# Plant_Reminder.net
KiCad netlist of a schematic drawn in EAGLE
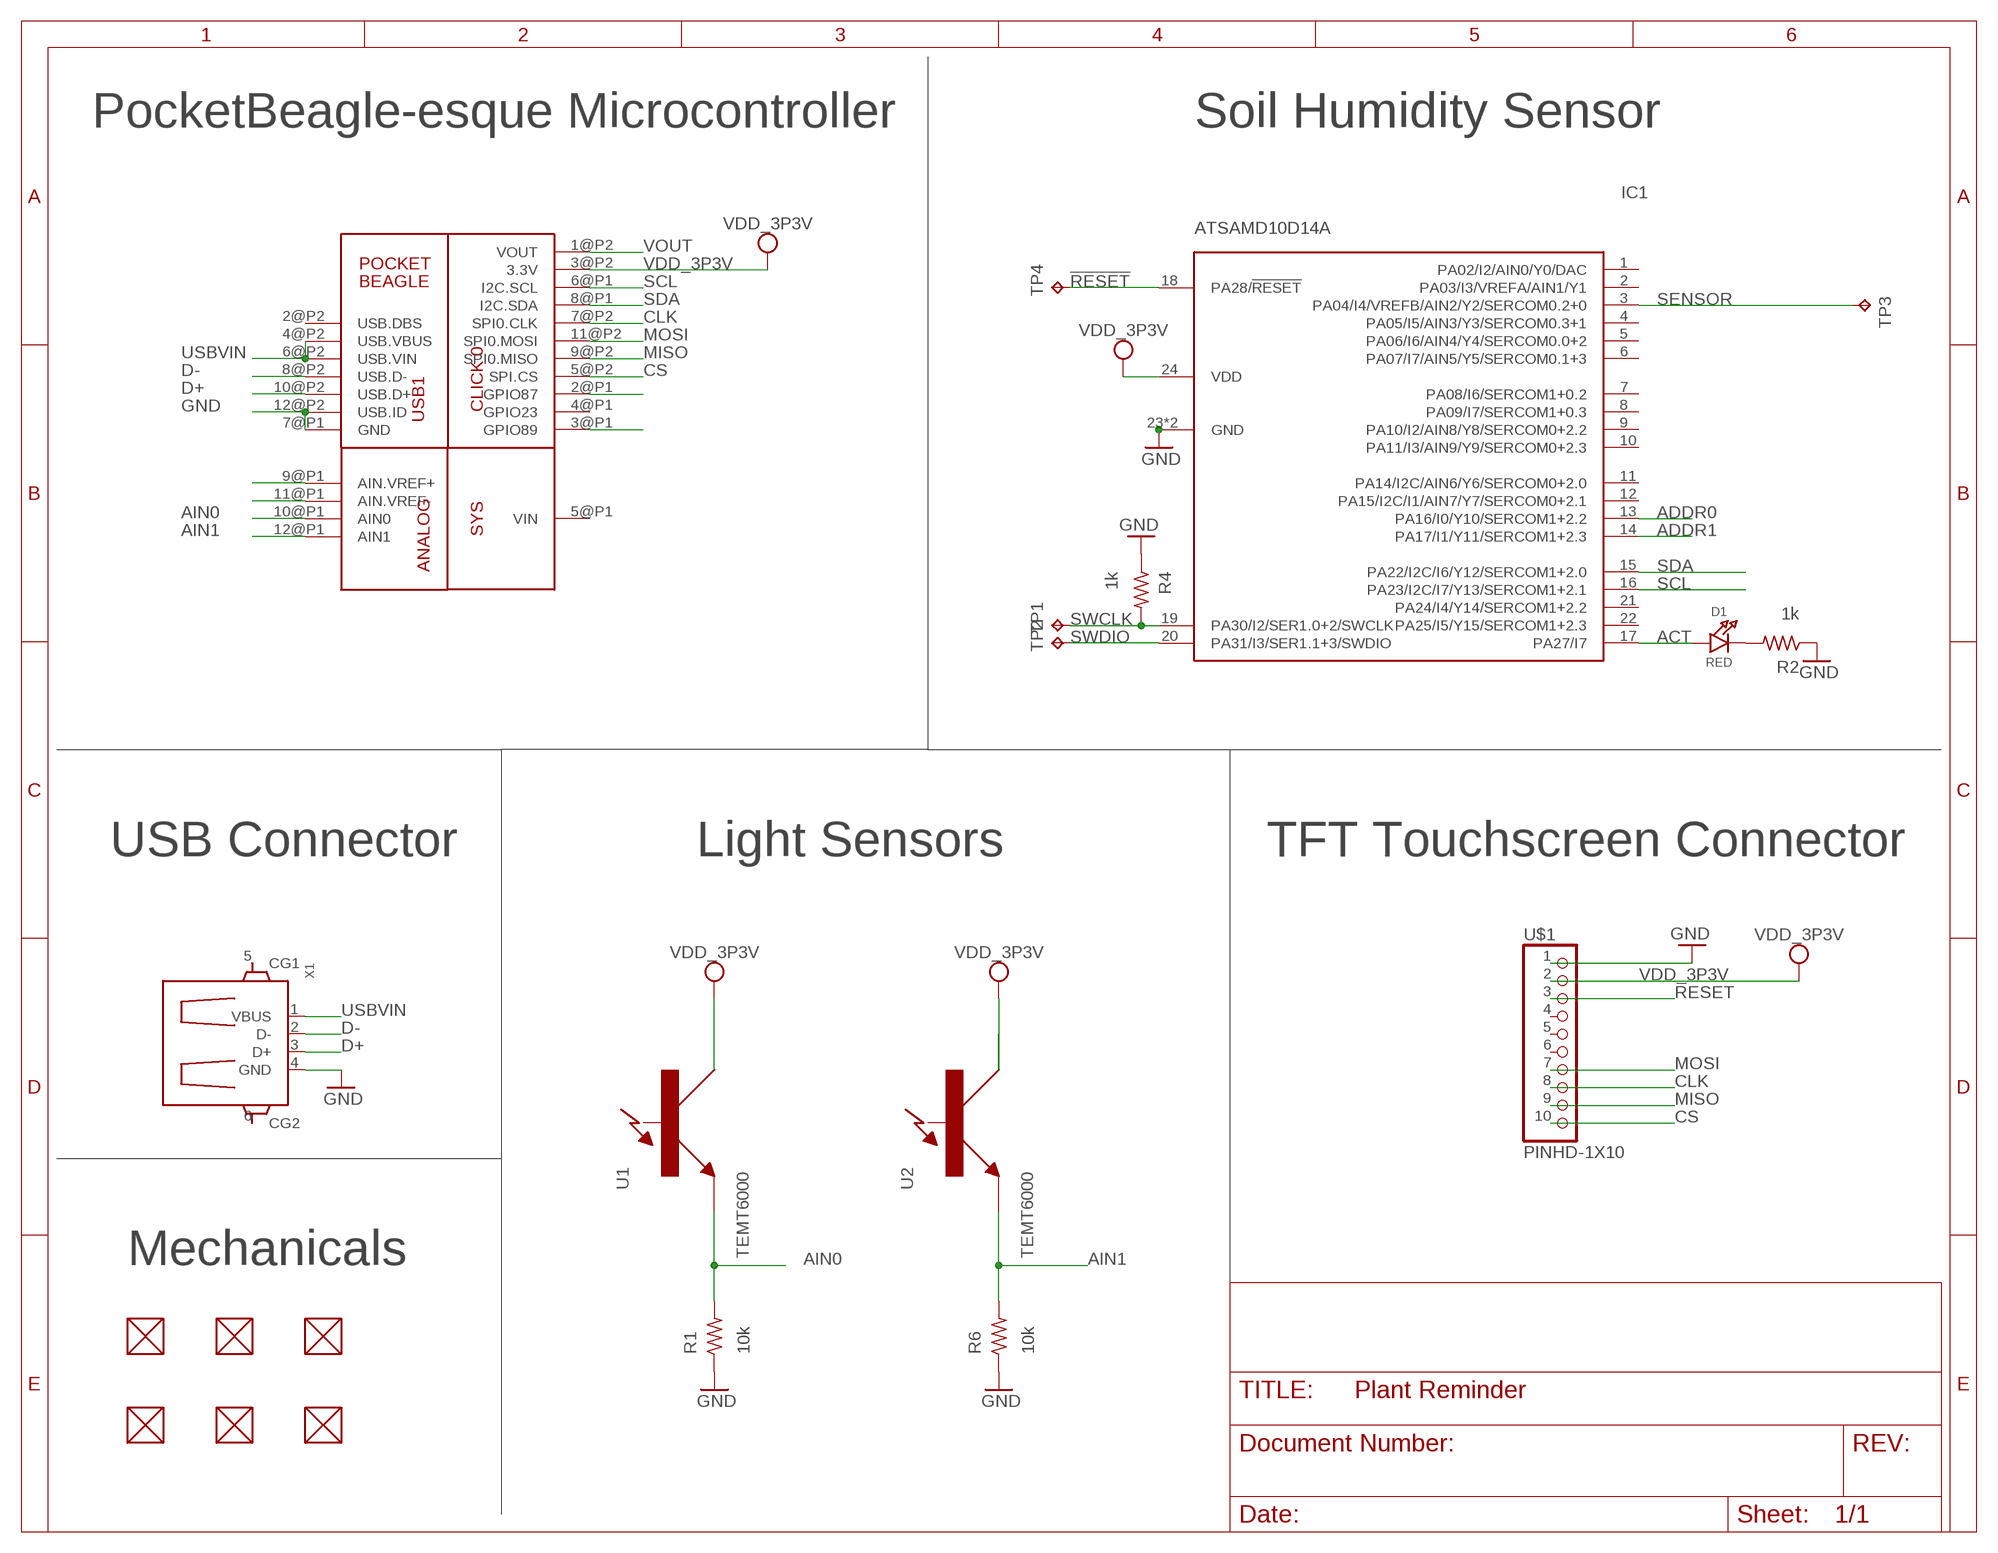
[diagram p0: schematic, sheet 1]

(export (version "E")
  (design (tool "Eeschema 10.0.6"))
  (components
    (comp (ref "D1")
      (value "RED")
      (footprint "eagle-import:CHIPLED_0805_NOOUTLINE")
      (libsource (lib "eagle-import") (part "LED0805_NOOUTLINE"))
    )
    (comp (ref "FUD1")
      (value "FIDUCIAL")
      (footprint "eagle-import:FIDUCIAL_40MIL")
      (libsource (lib "eagle-import") (part "FIDUCIAL"))
    )
    (comp (ref "FUD2")
      (value "FIDUCIAL")
      (footprint "eagle-import:FIDUCIAL_40MIL")
      (libsource (lib "eagle-import") (part "FIDUCIAL"))
    )
    (comp (ref "FUD3")
      (value "FIDUCIAL")
      (footprint "eagle-import:FIDUCIAL_40MIL")
      (libsource (lib "eagle-import") (part "FIDUCIAL"))
    )
    (comp (ref "FUD4")
      (value "FIDUCIAL")
      (footprint "eagle-import:FIDUCIAL_40MIL")
      (libsource (lib "eagle-import") (part "FIDUCIAL"))
    )
    (comp (ref "FUD5")
      (value "FIDUCIAL")
      (footprint "eagle-import:FIDUCIAL_40MIL")
      (libsource (lib "eagle-import") (part "FIDUCIAL"))
    )
    (comp (ref "FUD6")
      (value "FIDUCIAL")
      (footprint "eagle-import:FIDUCIAL_40MIL")
      (libsource (lib "eagle-import") (part "FIDUCIAL"))
    )
    (comp (ref "IC1")
      (value "ATSAMD10D14A")
      (footprint "eagle-import:QFN24_4MM")
      (libsource (lib "eagle-import") (part "ATSAMD10D14A"))
    )
    (comp (ref "R1")
      (value "10k")
      (footprint "eagle-import:R0402")
      (libsource (lib "eagle-import") (part "R_R0402"))
    )
    (comp (ref "R2")
      (value "1k")
      (footprint "eagle-import:R0402")
      (libsource (lib "eagle-import") (part "R_R0402"))
    )
    (comp (ref "R4")
      (value "1k")
      (footprint "eagle-import:R0402")
      (libsource (lib "eagle-import") (part "R_R0402"))
    )
    (comp (ref "R6")
      (value "10k")
      (footprint "eagle-import:R0402")
      (libsource (lib "eagle-import") (part "R_R0402"))
    )
    (comp (ref "TP1")
      (value "TPTP15R")
      (footprint "eagle-import:TP15R")
      (libsource (lib "eagle-import") (part "TPTP15R"))
    )
    (comp (ref "TP2")
      (value "TPTP15R")
      (footprint "eagle-import:TP15R")
      (libsource (lib "eagle-import") (part "TPTP15R"))
    )
    (comp (ref "TP3")
      (value "TPTP10R")
      (footprint "eagle-import:TP10R")
      (libsource (lib "eagle-import") (part "TPTP10R"))
    )
    (comp (ref "TP4")
      (value "TPTP15R")
      (footprint "eagle-import:TP15R")
      (libsource (lib "eagle-import") (part "TPTP15R"))
    )
    (comp (ref "U$1")
      (value "PINHD-1X10")
      (footprint "eagle-import:1X10-BIG")
      (libsource (lib "eagle-import") (part "PINHD-1X10"))
    )
    (comp (ref "U1")
      (value "TEMT6000")
      (footprint "eagle-import:TEMT6000")
      (libsource (lib "eagle-import") (part "TEMT6000"))
    )
    (comp (ref "U2")
      (value "TEMT6000")
      (footprint "eagle-import:TEMT6000")
      (libsource (lib "eagle-import") (part "TEMT6000"))
    )
    (comp (ref "U3")
      (value "POCKETBEAGLE")
      (footprint "eagle-import:POCKETBEAGLE")
      (libsource (lib "eagle-import") (part "POCKETBEAGLE"))
    )
    (comp (ref "X1")
      (value "GHI2_USB_HOST_W/CHASSIS_GND")
      (footprint "eagle-import:GHI2_USB_HOST_HORIZONTAL_W_CHASSIS_GND")
      (libsource (lib "eagle-import") (part "GHI2_USB_HOST_W/CHASSIS_GND"))
    )
  )
  (nets
    (net (code "1") (name "/ACT") (class "Default")
      (node (ref "D1") (pin "A") (pinfunction "A_A") (pintype "passive"))
      (node (ref "IC1") (pin "17") (pinfunction "PA27/I7_17") (pintype "bidirectional"))
    )
    (net (code "2") (name "/ADDR0") (class "Default")
      (node (ref "IC1") (pin "13") (pinfunction "PA16/I0/Y10/SERCOM1+2.2_13") (pintype "bidirectional"))
    )
    (net (code "3") (name "/ADDR1") (class "Default")
      (node (ref "IC1") (pin "14") (pinfunction "PA17/I1/Y11/SERCOM1+2.3_14") (pintype "bidirectional"))
    )
    (net (code "4") (name "/AIN0") (class "Default")
      (node (ref "R1") (pin "2") (pinfunction "2_2") (pintype "passive"))
      (node (ref "U1") (pin "P$2") (pinfunction "P$2_P$2") (pintype "bidirectional"))
      (node (ref "U3") (pin "10@P1") (pinfunction "AIN0_10@P1") (pintype "bidirectional"))
    )
    (net (code "5") (name "/AIN1") (class "Default")
      (node (ref "R6") (pin "2") (pinfunction "2_2") (pintype "passive"))
      (node (ref "U2") (pin "P$2") (pinfunction "P$2_P$2") (pintype "bidirectional"))
      (node (ref "U3") (pin "12@P1") (pinfunction "AIN1_12@P1") (pintype "bidirectional"))
    )
    (net (code "6") (name "/CLK") (class "Default")
      (node (ref "U$1") (pin "8") (pinfunction "8_8") (pintype "passive"))
      (node (ref "U3") (pin "7@P2") (pinfunction "SPI0.CLK_7@P2") (pintype "bidirectional"))
    )
    (net (code "7") (name "/CS") (class "Default")
      (node (ref "U$1") (pin "10") (pinfunction "10_10") (pintype "passive"))
      (node (ref "U3") (pin "5@P2") (pinfunction "SPI.CS_5@P2") (pintype "bidirectional"))
    )
    (net (code "8") (name "/D+") (class "Default")
      (node (ref "U3") (pin "10@P2") (pinfunction "USB.D+_10@P2") (pintype "bidirectional"))
      (node (ref "X1") (pin "3") (pinfunction "D+_3") (pintype "bidirectional"))
    )
    (net (code "9") (name "/D-") (class "Default")
      (node (ref "U3") (pin "8@P2") (pinfunction "USB.D-_8@P2") (pintype "bidirectional"))
      (node (ref "X1") (pin "2") (pinfunction "D-_2") (pintype "bidirectional"))
    )
    (net (code "10") (name "/MISO") (class "Default")
      (node (ref "U$1") (pin "9") (pinfunction "9_9") (pintype "passive"))
      (node (ref "U3") (pin "9@P2") (pinfunction "SPI0.MISO_9@P2") (pintype "bidirectional"))
    )
    (net (code "11") (name "/MOSI") (class "Default")
      (node (ref "U$1") (pin "7") (pinfunction "7_7") (pintype "passive"))
      (node (ref "U3") (pin "11@P2") (pinfunction "SPI0.MOSI_11@P2") (pintype "bidirectional"))
    )
    (net (code "12") (name "/RESET") (class "Default")
      (node (ref "U$1") (pin "3") (pinfunction "3_3") (pintype "passive"))
      (node (ref "U3") (pin "2@P1") (pinfunction "GPIO87_2@P1") (pintype "bidirectional"))
    )
    (net (code "13") (name "/SCL") (class "Default")
      (node (ref "IC1") (pin "16") (pinfunction "PA23/I2C/I7/Y13/SERCOM1+2.1_16") (pintype "bidirectional"))
      (node (ref "U3") (pin "6@P1") (pinfunction "I2C.SCL_6@P1") (pintype "bidirectional"))
    )
    (net (code "14") (name "/SDA") (class "Default")
      (node (ref "IC1") (pin "15") (pinfunction "PA22/I2C/I6/Y12/SERCOM1+2.0_15") (pintype "bidirectional"))
      (node (ref "U3") (pin "8@P1") (pinfunction "I2C.SDA_8@P1") (pintype "bidirectional"))
    )
    (net (code "15") (name "/SENSOR") (class "Default")
      (node (ref "IC1") (pin "3") (pinfunction "PA04/I4/VREFB/AIN2/Y2/SERCOM0.2+0_3") (pintype "bidirectional"))
      (node (ref "TP3") (pin "TP") (pinfunction "TP_TP") (pintype "input"))
    )
    (net (code "16") (name "/SWCLK") (class "Default")
      (node (ref "IC1") (pin "19") (pinfunction "PA30/I2/SER1.0+2/SWCLK_19") (pintype "bidirectional"))
      (node (ref "R4") (pin "2") (pinfunction "2_2") (pintype "passive"))
      (node (ref "TP1") (pin "TP") (pinfunction "TP_TP") (pintype "input"))
    )
    (net (code "17") (name "/SWDIO") (class "Default")
      (node (ref "IC1") (pin "20") (pinfunction "PA31/I3/SER1.1+3/SWDIO_20") (pintype "bidirectional"))
      (node (ref "TP2") (pin "TP") (pinfunction "TP_TP") (pintype "input"))
    )
    (net (code "18") (name "/USBVIN") (class "Default")
      (node (ref "U3") (pin "4@P2") (pinfunction "USB.VBUS_4@P2") (pintype "bidirectional"))
      (node (ref "U3") (pin "6@P2") (pinfunction "USB.VIN_6@P2") (pintype "bidirectional"))
      (node (ref "X1") (pin "1") (pinfunction "VBUS_1") (pintype "bidirectional"))
    )
    (net (code "19") (name "/VOUT") (class "Default")
      (node (ref "U3") (pin "1@P2") (pinfunction "VOUT_1@P2") (pintype "bidirectional"))
    )
    (net (code "20") (name "/~{RESET}") (class "Default")
      (node (ref "IC1") (pin "18") (pinfunction "PA28/~{RESET}_18") (pintype "bidirectional"))
      (node (ref "TP4") (pin "TP") (pinfunction "TP_TP") (pintype "input"))
    )
    (net (code "21") (name "GND") (class "Default")
      (node (ref "IC1") (pin "23") (pinfunction "GND_23") (pintype "power_in"))
      (node (ref "IC1") (pin "THERM") (pinfunction "GND_THERM") (pintype "power_in"))
      (node (ref "R1") (pin "1") (pinfunction "1_1") (pintype "passive"))
      (node (ref "R2") (pin "1") (pinfunction "1_1") (pintype "passive"))
      (node (ref "R4") (pin "1") (pinfunction "1_1") (pintype "passive"))
      (node (ref "R6") (pin "1") (pinfunction "1_1") (pintype "passive"))
      (node (ref "U$1") (pin "1") (pinfunction "1_1") (pintype "passive"))
      (node (ref "U3") (pin "12@P2") (pinfunction "USB.ID_12@P2") (pintype "bidirectional"))
      (node (ref "U3") (pin "7@P1") (pinfunction "GND_7@P1") (pintype "bidirectional"))
      (node (ref "X1") (pin "4") (pinfunction "GND_4") (pintype "bidirectional"))
    )
    (net (code "22") (name "Net-(D1-PadC)") (class "Default")
      (node (ref "D1") (pin "C") (pinfunction "C_C") (pintype "passive"))
      (node (ref "R2") (pin "2") (pinfunction "2_2") (pintype "passive"))
    )
    (net (code "23") (name "VDD_3P3V") (class "Default")
      (node (ref "IC1") (pin "24") (pinfunction "VDD_24") (pintype "power_in"))
      (node (ref "U$1") (pin "2") (pinfunction "2_2") (pintype "passive"))
      (node (ref "U1") (pin "P$1") (pinfunction "P$1_P$1") (pintype "bidirectional"))
      (node (ref "U2") (pin "P$1") (pinfunction "P$1_P$1") (pintype "bidirectional"))
      (node (ref "U3") (pin "3@P2") (pinfunction "3.3V_3@P2") (pintype "bidirectional"))
    )
    (net (code "24") (name "unconnected-(FUD1-PadP$1)") (class "Default")
      (node (ref "FUD1") (pin "P$1") (pinfunction "P$1_P$1") (pintype "no_connect"))
    )
    (net (code "25") (name "unconnected-(FUD2-PadP$1)") (class "Default")
      (node (ref "FUD2") (pin "P$1") (pinfunction "P$1_P$1") (pintype "no_connect"))
    )
    (net (code "26") (name "unconnected-(FUD3-PadP$1)") (class "Default")
      (node (ref "FUD3") (pin "P$1") (pinfunction "P$1_P$1") (pintype "no_connect"))
    )
    (net (code "27") (name "unconnected-(FUD4-PadP$1)") (class "Default")
      (node (ref "FUD4") (pin "P$1") (pinfunction "P$1_P$1") (pintype "no_connect"))
    )
    (net (code "28") (name "unconnected-(FUD5-PadP$1)") (class "Default")
      (node (ref "FUD5") (pin "P$1") (pinfunction "P$1_P$1") (pintype "no_connect"))
    )
    (net (code "29") (name "unconnected-(FUD6-PadP$1)") (class "Default")
      (node (ref "FUD6") (pin "P$1") (pinfunction "P$1_P$1") (pintype "no_connect"))
    )
    (net (code "30") (name "unconnected-(IC1-PA02{slash}I2{slash}AIN0{slash}Y0{slash}DAC-Pad1)") (class "Default")
      (node (ref "IC1") (pin "1") (pinfunction "PA02/I2/AIN0/Y0/DAC_1") (pintype "bidirectional"))
    )
    (net (code "31") (name "unconnected-(IC1-PA03{slash}I3{slash}VREFA{slash}AIN1{slash}Y1-Pad2)") (class "Default")
      (node (ref "IC1") (pin "2") (pinfunction "PA03/I3/VREFA/AIN1/Y1_2") (pintype "bidirectional"))
    )
    (net (code "32") (name "unconnected-(IC1-PA05{slash}I5{slash}AIN3{slash}Y3{slash}SERCOM0.3+1-Pad4)") (class "Default")
      (node (ref "IC1") (pin "4") (pinfunction "PA05/I5/AIN3/Y3/SERCOM0.3+1_4") (pintype "bidirectional"))
    )
    (net (code "33") (name "unconnected-(IC1-PA06{slash}I6{slash}AIN4{slash}Y4{slash}SERCOM0.0+2-Pad5)") (class "Default")
      (node (ref "IC1") (pin "5") (pinfunction "PA06/I6/AIN4/Y4/SERCOM0.0+2_5") (pintype "bidirectional"))
    )
    (net (code "34") (name "unconnected-(IC1-PA07{slash}I7{slash}AIN5{slash}Y5{slash}SERCOM0.1+3-Pad6)") (class "Default")
      (node (ref "IC1") (pin "6") (pinfunction "PA07/I7/AIN5/Y5/SERCOM0.1+3_6") (pintype "bidirectional"))
    )
    (net (code "35") (name "unconnected-(IC1-PA08{slash}I6{slash}SERCOM1+0.2-Pad7)") (class "Default")
      (node (ref "IC1") (pin "7") (pinfunction "PA08/I6/SERCOM1+0.2_7") (pintype "bidirectional"))
    )
    (net (code "36") (name "unconnected-(IC1-PA09{slash}I7{slash}SERCOM1+0.3-Pad8)") (class "Default")
      (node (ref "IC1") (pin "8") (pinfunction "PA09/I7/SERCOM1+0.3_8") (pintype "bidirectional"))
    )
    (net (code "37") (name "unconnected-(IC1-PA10{slash}I2{slash}AIN8{slash}Y8{slash}SERCOM0+2.2-Pad9)") (class "Default")
      (node (ref "IC1") (pin "9") (pinfunction "PA10/I2/AIN8/Y8/SERCOM0+2.2_9") (pintype "bidirectional"))
    )
    (net (code "38") (name "unconnected-(IC1-PA11{slash}I3{slash}AIN9{slash}Y9{slash}SERCOM0+2.3-Pad10)") (class "Default")
      (node (ref "IC1") (pin "10") (pinfunction "PA11/I3/AIN9/Y9/SERCOM0+2.3_10") (pintype "bidirectional"))
    )
    (net (code "39") (name "unconnected-(IC1-PA14{slash}I2C{slash}AIN6{slash}Y6{slash}SERCOM0+2.0-Pad11)") (class "Default")
      (node (ref "IC1") (pin "11") (pinfunction "PA14/I2C/AIN6/Y6/SERCOM0+2.0_11") (pintype "bidirectional"))
    )
    (net (code "40") (name "unconnected-(IC1-PA15{slash}I2C{slash}I1{slash}AIN7{slash}Y7{slash}SERCOM0+2.1-Pad12)") (class "Default")
      (node (ref "IC1") (pin "12") (pinfunction "PA15/I2C/I1/AIN7/Y7/SERCOM0+2.1_12") (pintype "bidirectional"))
    )
    (net (code "41") (name "unconnected-(IC1-PA24{slash}I4{slash}Y14{slash}SERCOM1+2.2-Pad21)") (class "Default")
      (node (ref "IC1") (pin "21") (pinfunction "PA24/I4/Y14/SERCOM1+2.2_21") (pintype "bidirectional"))
    )
    (net (code "42") (name "unconnected-(IC1-PA25{slash}I5{slash}Y15{slash}SERCOM1+2.3-Pad22)") (class "Default")
      (node (ref "IC1") (pin "22") (pinfunction "PA25/I5/Y15/SERCOM1+2.3_22") (pintype "bidirectional"))
    )
    (net (code "43") (name "unconnected-(U$1-Pad4)") (class "Default")
      (node (ref "U$1") (pin "4") (pinfunction "4_4") (pintype "passive"))
    )
    (net (code "44") (name "unconnected-(U$1-Pad5)") (class "Default")
      (node (ref "U$1") (pin "5") (pinfunction "5_5") (pintype "passive"))
    )
    (net (code "45") (name "unconnected-(U$1-Pad6)") (class "Default")
      (node (ref "U$1") (pin "6") (pinfunction "6_6") (pintype "passive"))
    )
    (net (code "46") (name "unconnected-(U1-PadP$3)") (class "Default")
      (node (ref "U1") (pin "P$3") (pinfunction "P$3_P$3") (pintype "bidirectional"))
    )
    (net (code "47") (name "unconnected-(U2-PadP$3)") (class "Default")
      (node (ref "U2") (pin "P$3") (pinfunction "P$3_P$3") (pintype "bidirectional"))
    )
    (net (code "48") (name "unconnected-(U3-AIN.VREF+-Pad9@P1)") (class "Default")
      (node (ref "U3") (pin "9@P1") (pinfunction "AIN.VREF+_9@P1") (pintype "bidirectional"))
    )
    (net (code "49") (name "unconnected-(U3-AIN.VREF--Pad11@P1)") (class "Default")
      (node (ref "U3") (pin "11@P1") (pinfunction "AIN.VREF-_11@P1") (pintype "bidirectional"))
    )
    (net (code "50") (name "unconnected-(U3-GPIO23-Pad4@P1)") (class "Default")
      (node (ref "U3") (pin "4@P1") (pinfunction "GPIO23_4@P1") (pintype "bidirectional"))
    )
    (net (code "51") (name "unconnected-(U3-GPIO89-Pad3@P1)") (class "Default")
      (node (ref "U3") (pin "3@P1") (pinfunction "GPIO89_3@P1") (pintype "bidirectional"))
    )
    (net (code "52") (name "unconnected-(U3-USB.DBS-Pad2@P2)") (class "Default")
      (node (ref "U3") (pin "2@P2") (pinfunction "USB.DBS_2@P2") (pintype "bidirectional"))
    )
    (net (code "53") (name "unconnected-(U3-VIN-Pad5@P1)") (class "Default")
      (node (ref "U3") (pin "5@P1") (pinfunction "VIN_5@P1") (pintype "bidirectional"))
    )
    (net (code "54") (name "unconnected-(X1-CG1-Pad5)") (class "Default")
      (node (ref "X1") (pin "5") (pinfunction "CG1_5") (pintype "bidirectional"))
    )
    (net (code "55") (name "unconnected-(X1-CG2-Pad6)") (class "Default")
      (node (ref "X1") (pin "6") (pinfunction "CG2_6") (pintype "bidirectional"))
    )
  )
)
